# Connectors.net
KiCad netlist of a schematic drawn in Altium Designer
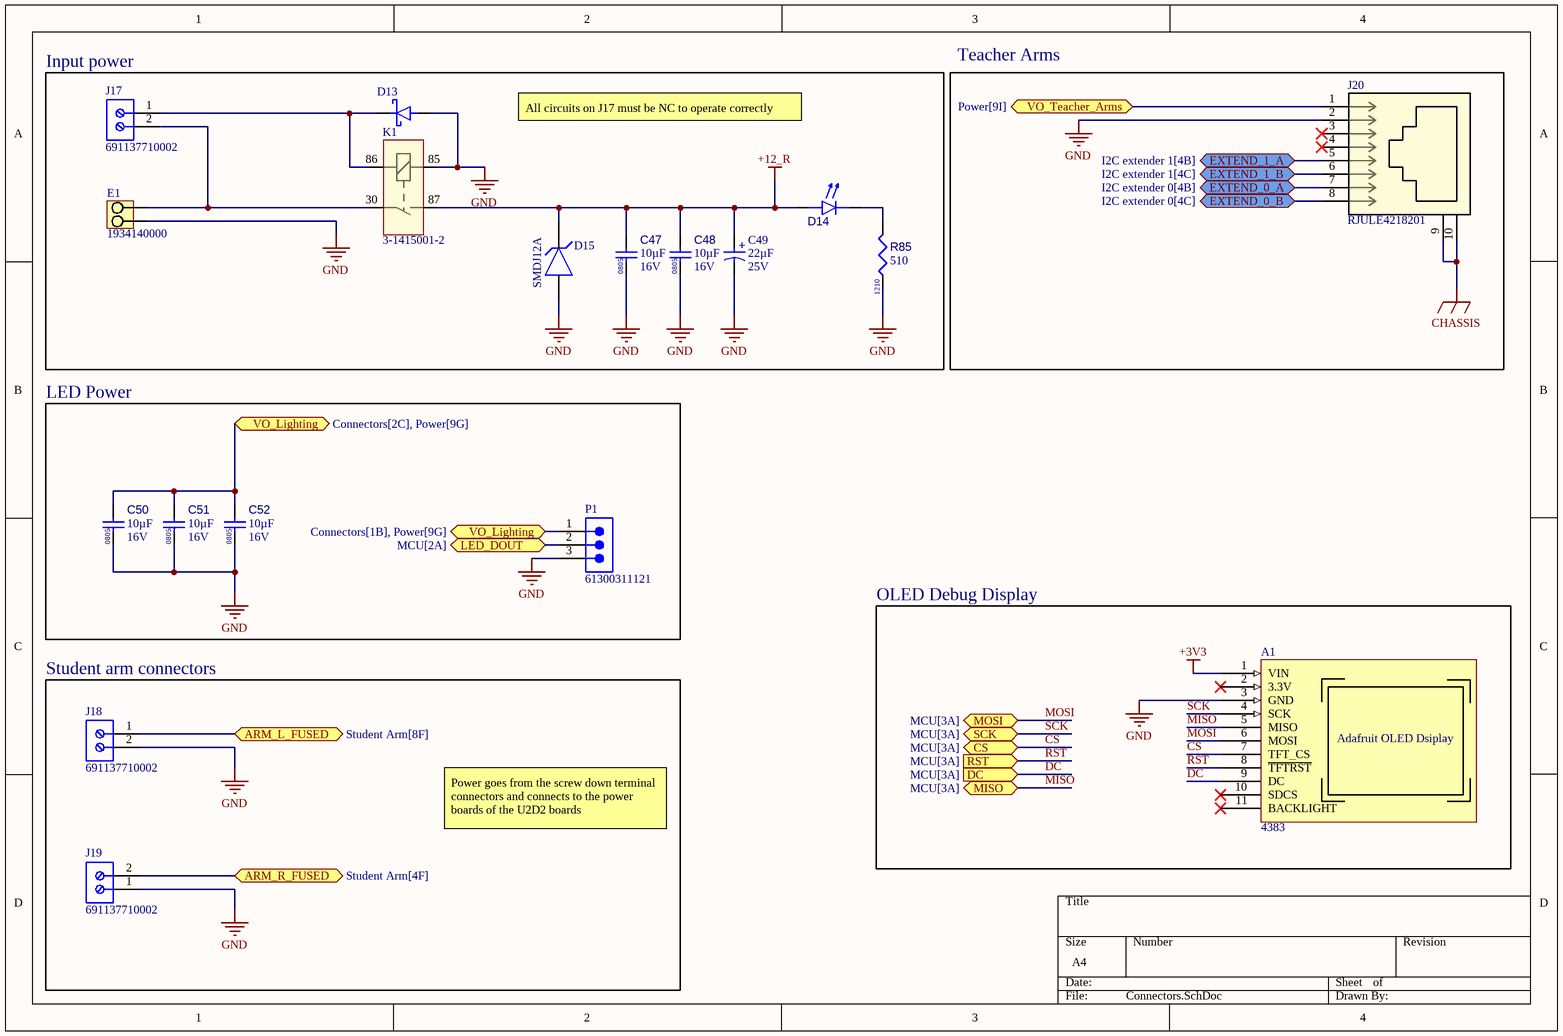
[diagram p0: Connectors.SchDoc]

(export (version "E")
  (design (tool "Eeschema 10.0.6"))
  (components
    (comp (ref "A1")
      (value "4383")
      (footprint "4383-Footprint-1")
      (description "Adafruit OLED display")
      (libsource (lib "hawaiirobotics") (part "4383-Symbol-1"))
    )
    (comp (ref "C47")
      (value "10µF")
      (footprint "CAP CER 10UF 16V X5R 0805-Footprint-1")
      (fields
        (field (name "VOLTAGE RATING") "16V")
        (field (name "CASE/PACKAGE") "0805")
        (field (name "Comment") "CAP CER 10UF 16V X5R 0805")
      )
      (libsource (lib "hawaiirobotics") (part "CAP-NP-2"))
    )
    (comp (ref "C48")
      (value "10µF")
      (footprint "CAP CER 10UF 16V X5R 0805-Footprint-1")
      (fields
        (field (name "VOLTAGE RATING") "16V")
        (field (name "CASE/PACKAGE") "0805")
        (field (name "Comment") "CAP CER 10UF 16V X5R 0805")
      )
      (libsource (lib "hawaiirobotics") (part "CAP-NP-2"))
    )
    (comp (ref "C49")
      (value "22µF")
      (footprint "WCAP-PSLP_D6.3H5.8")
      (description "22 µF 25 V Aluminum - Polymer Capacitors Radial, Can - SMD 30mOhm 2000 Hrs @ 105°C")
      (fields
        (field (name "TOLERANCE") "20%")
        (field (name "VOLTAGE RATING") "25V")
        (field (name "Comment") "875105544003")
      )
      (libsource (lib "hawaiirobotics") (part "Capacitor_Polarized"))
    )
    (comp (ref "C50")
      (value "10µF")
      (footprint "CAP CER 10UF 16V X5R 0805-Footprint-1")
      (fields
        (field (name "VOLTAGE RATING") "16V")
        (field (name "CASE/PACKAGE") "0805")
        (field (name "Comment") "CAP CER 10UF 16V X5R 0805")
      )
      (libsource (lib "hawaiirobotics") (part "CAP-NP-2"))
    )
    (comp (ref "C51")
      (value "10µF")
      (footprint "CAP CER 10UF 16V X5R 0805-Footprint-1")
      (fields
        (field (name "VOLTAGE RATING") "16V")
        (field (name "CASE/PACKAGE") "0805")
        (field (name "Comment") "CAP CER 10UF 16V X5R 0805")
      )
      (libsource (lib "hawaiirobotics") (part "CAP-NP-2"))
    )
    (comp (ref "C52")
      (value "10µF")
      (footprint "CAP CER 10UF 16V X5R 0805-Footprint-1")
      (fields
        (field (name "VOLTAGE RATING") "16V")
        (field (name "CASE/PACKAGE") "0805")
        (field (name "Comment") "CAP CER 10UF 16V X5R 0805")
      )
      (libsource (lib "hawaiirobotics") (part "CAP-NP-2"))
    )
    (comp (ref "D13")
      (value "VS-10BQ015-M3/5BT")
      (footprint "FP-95401-MFG")
      (description "Rectifier Diode, Schottky, 1 Phase, 1 Element, 1A, 15V V(RRM), Silicon")
      (libsource (lib "hawaiirobotics") (part "VS-10BQ015-M3/5BT-Symbol-1"))
    )
    (comp (ref "D14")
      (value "150060RS75000")
      (footprint "WL-SMCW_0603_150060xx75000")
      (description "Single Color LED, Red, Water Clear, 1.1mm")
      (libsource (lib "hawaiirobotics") (part "DIODE-LED-2"))
    )
    (comp (ref "D15")
      (value "SMDJ12A")
      (footprint "FP-DO-214AB_SMC_J-Bend-MFG")
      (description "Trans Voltage Suppressor Diode, 3000W, 12V V(RWM), Unidirectional, 1 Element, Silicon, DO-214AB")
      (libsource (lib "hawaiirobotics") (part "SMDJ12A-Symbol-1"))
    )
    (comp (ref "E1")
      (value "1934140000")
      (footprint "LU_10_16_90_02")
      (description "OMNIMATE Power - series LU")
      (fields (field (name "MANUFACTURER") "Weidmueller"))
      (libsource (lib "Altium Content Vault") (part "Terminal_02_1x02"))
    )
    (comp (ref "J17")
      (value "691137710002")
      (footprint "691137710002")
      (description "Series 1377 - 5.00 mm Horizontal Entry with Pressure Clamp WR-TBL, 2 pin")
      (libsource (lib "hawaiirobotics") (part "TBL - 1R - 02P - Screw"))
    )
    (comp (ref "J18")
      (value "691137710002")
      (footprint "691137710002")
      (description "Series 1377 - 5.00 mm Horizontal Entry with Pressure Clamp WR-TBL, 2 pin")
      (libsource (lib "hawaiirobotics") (part "TBL - 1R - 02P - Screw"))
    )
    (comp (ref "J19")
      (value "691137710002")
      (footprint "691137710002")
      (description "Series 1377 - 5.00 mm Horizontal Entry with Pressure Clamp WR-TBL, 2 pin")
      (libsource (lib "hawaiirobotics") (part "TBL - 1R - 02P - Screw"))
    )
    (comp (ref "J20")
      (value "RJULE4218201")
      (footprint "RJULE4218201-Footprint-1")
      (description "Modular Jack - Right Angle, Input Output Connectors RJ45, 8P8C, Without LEDs, Shield.")
      (libsource (lib "hawaiirobotics") (part "RJULE4218201-Symbol-1"))
    )
    (comp (ref "K1")
      (value "3-1415001-2")
      (footprint "3-1415001-2-Footprint-1")
      (libsource (lib "hawaiirobotics") (part "3-1415001-2-Symbol-1"))
    )
    (comp (ref "P1")
      (value "61300311121")
      (footprint "61300311121")
      (libsource (lib "hawaiirobotics") (part "Header_Male_1R_03P"))
    )
    (comp (ref "R85")
      (value "510")
      (footprint "RESC3126X60X50NL10T20")
      (fields
        (field (name "CASE/PACKAGE") "1210")
        (field (name "POWER") "500mW")
        (field (name "TOLERANCE") "5%")
        (field (name "Comment") "RC1210JR-07510RL")
      )
      (libsource (lib "hawaiirobotics") (part "RES-2"))
    )
  )
  (nets
    (net (code "1") (name "+3V3") (class "Default")
      (node (ref "A1") (pin "1") (pinfunction "VIN_1") (pintype "input"))
    )
    (net (code "2") (name "+12_R") (class "Default")
      (node (ref "C47") (pin "2") (pinfunction "2_2") (pintype "passive"))
      (node (ref "C48") (pin "2") (pinfunction "2_2") (pintype "passive"))
      (node (ref "C49") (pin "1") (pinfunction "P_1") (pintype "passive"))
      (node (ref "D14") (pin "2") (pinfunction "A_2") (pintype "passive"))
      (node (ref "D15") (pin "1") (pinfunction "C_1") (pintype "passive"))
      (node (ref "K1") (pin "87") (pinfunction "87_87") (pintype "passive"))
    )
    (net (code "3") (name "/ARM_L_FUSED") (class "Default")
      (node (ref "J18") (pin "1") (pinfunction "1_1") (pintype "passive"))
    )
    (net (code "4") (name "/ARM_R_FUSED") (class "Default")
      (node (ref "J19") (pin "2") (pinfunction "2_2") (pintype "passive"))
    )
    (net (code "5") (name "/CS") (class "Default")
      (node (ref "A1") (pin "7") (pinfunction "TFT_CS_7") (pintype "passive"))
    )
    (net (code "6") (name "/DC") (class "Default")
      (node (ref "A1") (pin "9") (pinfunction "DC_9") (pintype "passive"))
    )
    (net (code "7") (name "/EXTEND_0_A") (class "Default")
      (node (ref "J20") (pin "7") (pinfunction "7_7") (pintype "passive"))
    )
    (net (code "8") (name "/EXTEND_0_B") (class "Default")
      (node (ref "J20") (pin "8") (pinfunction "8_8") (pintype "passive"))
    )
    (net (code "9") (name "/EXTEND_1_A") (class "Default")
      (node (ref "J20") (pin "5") (pinfunction "5_5") (pintype "passive"))
    )
    (net (code "10") (name "/EXTEND_1_B") (class "Default")
      (node (ref "J20") (pin "6") (pinfunction "6_6") (pintype "passive"))
    )
    (net (code "11") (name "/LED_DOUT") (class "Default")
      (node (ref "P1") (pin "2") (pinfunction "2_2") (pintype "passive"))
    )
    (net (code "12") (name "/MISO") (class "Default")
      (node (ref "A1") (pin "5") (pinfunction "MISO_5") (pintype "passive"))
    )
    (net (code "13") (name "/MOSI") (class "Default")
      (node (ref "A1") (pin "6") (pinfunction "MOSI_6") (pintype "passive"))
    )
    (net (code "14") (name "/RST") (class "Default")
      (node (ref "A1") (pin "8") (pinfunction "~{TFTRST}_8") (pintype "passive"))
    )
    (net (code "15") (name "/SCK") (class "Default")
      (node (ref "A1") (pin "4") (pinfunction "SCK_4") (pintype "input"))
    )
    (net (code "16") (name "/VO_Lighting") (class "Default")
      (node (ref "C50") (pin "2") (pinfunction "2_2") (pintype "passive"))
      (node (ref "C51") (pin "2") (pinfunction "2_2") (pintype "passive"))
      (node (ref "C52") (pin "2") (pinfunction "2_2") (pintype "passive"))
      (node (ref "P1") (pin "1") (pinfunction "1_1") (pintype "passive"))
    )
    (net (code "17") (name "/VO_Teacher_Arms") (class "Default")
      (node (ref "J20") (pin "1") (pinfunction "1_1") (pintype "passive"))
    )
    (net (code "18") (name "CHASSIS") (class "Default")
      (node (ref "J20") (pin "10") (pinfunction "10_10") (pintype "passive"))
      (node (ref "J20") (pin "9") (pinfunction "9_9") (pintype "passive"))
    )
    (net (code "19") (name "GND") (class "Default")
      (node (ref "A1") (pin "3") (pinfunction "GND_3") (pintype "input"))
      (node (ref "C47") (pin "1") (pinfunction "1_1") (pintype "passive"))
      (node (ref "C48") (pin "1") (pinfunction "1_1") (pintype "passive"))
      (node (ref "C49") (pin "2") (pinfunction "N_2") (pintype "passive"))
      (node (ref "C50") (pin "1") (pinfunction "1_1") (pintype "passive"))
      (node (ref "C51") (pin "1") (pinfunction "1_1") (pintype "passive"))
      (node (ref "C52") (pin "1") (pinfunction "1_1") (pintype "passive"))
      (node (ref "D13") (pin "2") (pinfunction "A_2") (pintype "passive"))
      (node (ref "D15") (pin "2") (pinfunction "A_2") (pintype "passive"))
      (node (ref "E1") (pin "A2") (pinfunction "A2_A2") (pintype "passive"))
      (node (ref "J18") (pin "2") (pinfunction "2_2") (pintype "passive"))
      (node (ref "J19") (pin "1") (pinfunction "1_1") (pintype "passive"))
      (node (ref "J20") (pin "2") (pinfunction "2_2") (pintype "passive"))
      (node (ref "K1") (pin "85") (pinfunction "85_85") (pintype "passive"))
      (node (ref "P1") (pin "3") (pinfunction "3_3") (pintype "passive"))
      (node (ref "R85") (pin "1") (pinfunction "1_1") (pintype "passive"))
    )
    (net (code "20") (name "Net-(D13-C)") (class "Default")
      (node (ref "D13") (pin "1") (pinfunction "C_1") (pintype "passive"))
      (node (ref "J17") (pin "1") (pinfunction "1_1") (pintype "passive"))
      (node (ref "K1") (pin "86") (pinfunction "86_86") (pintype "passive"))
    )
    (net (code "21") (name "Net-(D14-K)") (class "Default")
      (node (ref "D14") (pin "1") (pinfunction "K_1") (pintype "passive"))
      (node (ref "R85") (pin "2") (pinfunction "2_2") (pintype "passive"))
    )
    (net (code "22") (name "Net-(E1-PadA1)") (class "Default")
      (node (ref "E1") (pin "A1") (pinfunction "A1_A1") (pintype "passive"))
      (node (ref "J17") (pin "2") (pinfunction "2_2") (pintype "passive"))
      (node (ref "K1") (pin "30") (pinfunction "30_30") (pintype "passive"))
    )
    (net (code "23") (name "unconnected-(A1-3.3V-Pad2)") (class "Default")
      (node (ref "A1") (pin "2") (pinfunction "3.3V_2") (pintype "input+no_connect"))
    )
    (net (code "24") (name "unconnected-(A1-BACKLIGHT-Pad11)") (class "Default")
      (node (ref "A1") (pin "11") (pinfunction "BACKLIGHT_11") (pintype "passive+no_connect"))
    )
    (net (code "25") (name "unconnected-(A1-SDCS-Pad10)") (class "Default")
      (node (ref "A1") (pin "10") (pinfunction "SDCS_10") (pintype "passive+no_connect"))
    )
    (net (code "26") (name "unconnected-(J20-Pad3)") (class "Default")
      (node (ref "J20") (pin "3") (pinfunction "3_3") (pintype "passive+no_connect"))
    )
    (net (code "27") (name "unconnected-(J20-Pad4)") (class "Default")
      (node (ref "J20") (pin "4") (pinfunction "4_4") (pintype "passive+no_connect"))
    )
  )
)
